# SSRC_v2.net
KiCad netlist of a schematic drawn in EasyEDA Pro
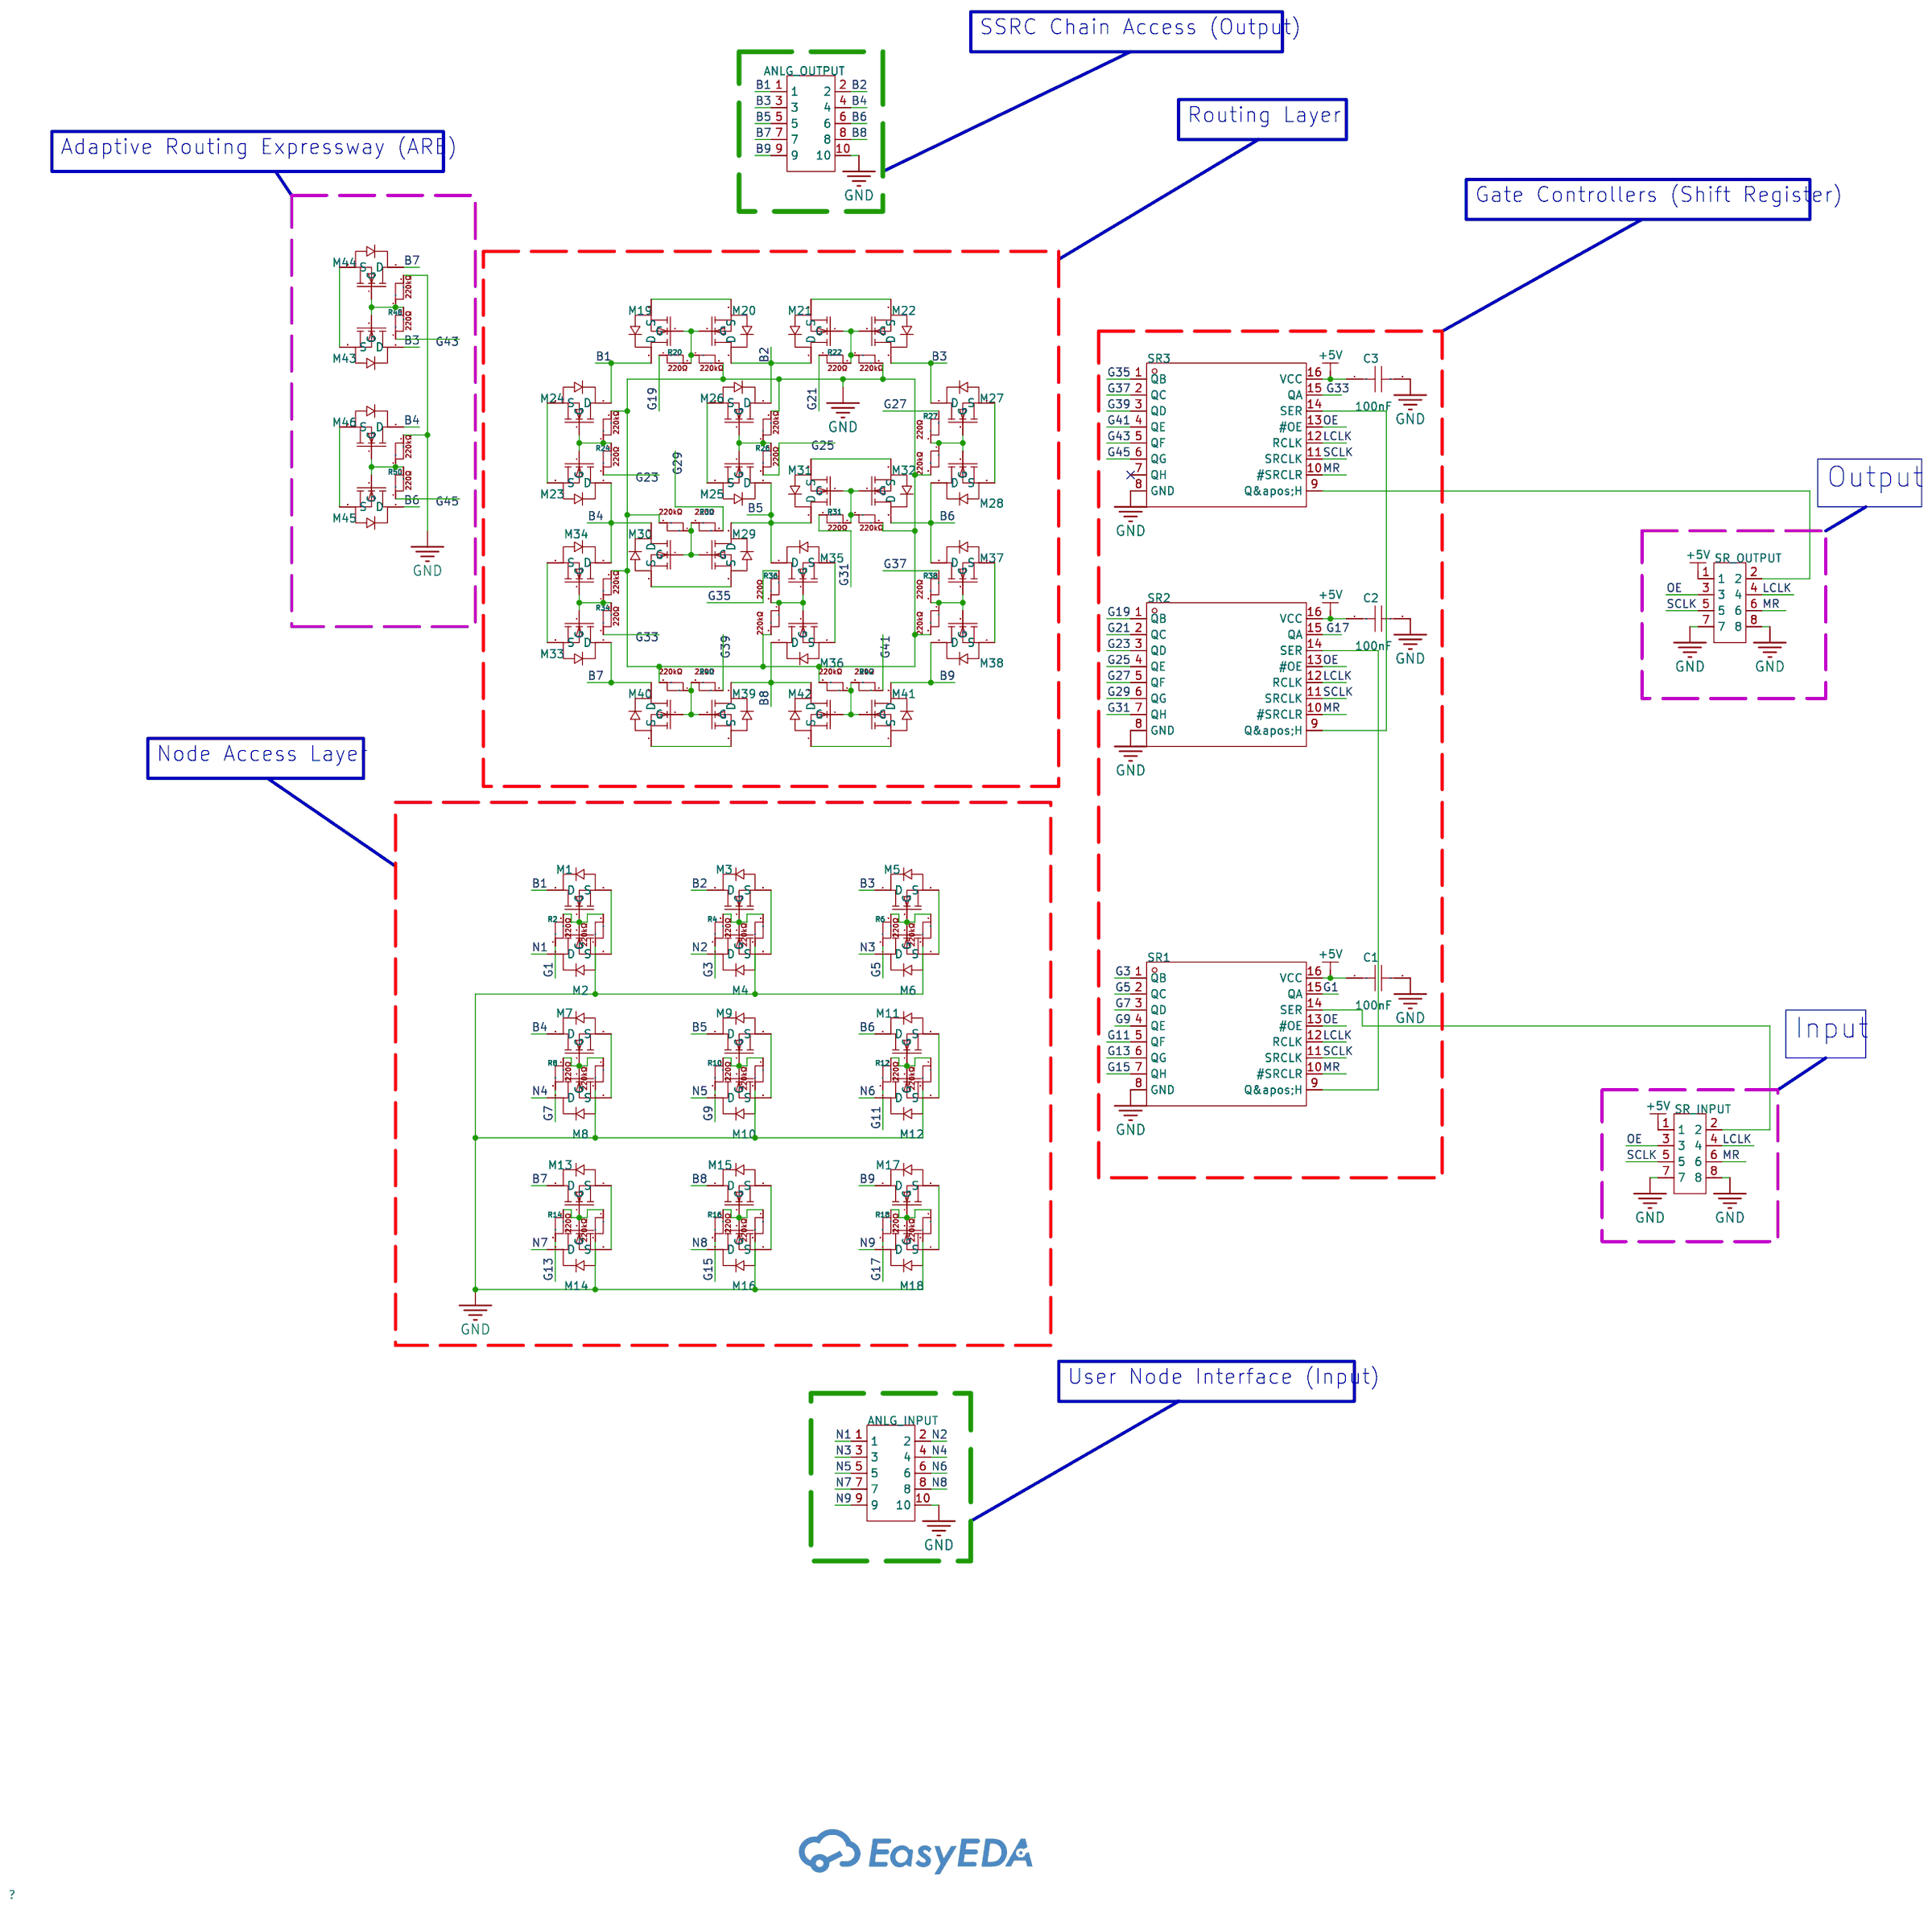
[diagram p0: schematic sheet]

(export (version "E")
  (design (tool "Eeschema 10.0.6"))
  (components
    (comp (ref "ANLG_INPUT")
      (value "PZ254V-12-10P")
      (footprint "easyedapro:HDR-TH_10P-P2.54-V-M-R2-C5-S2.54")
      (fields (field (name "Manufacturer") "XFCN(兴飞)"))
      (libsource (lib "easyedapro") (part "PZ254V-12-10P"))
    )
    (comp (ref "ANLG_OUTPUT")
      (value "PZ254V-12-10P")
      (footprint "easyedapro:HDR-TH_10P-P2.54-V-M-R2-C5-S2.54")
      (fields (field (name "Manufacturer") "XFCN(兴飞)"))
      (libsource (lib "easyedapro") (part "PZ254V-12-10P"))
    )
    (comp (ref "C1")
      (value "100nF")
      (footprint "easyedapro:C0805")
      (description "Capacitance:100nF Tolerance:±10% Tolerance:±10% Voltage Rating:50V Temperature Coefficient:X7R")
      (fields
        (field (name "Manufacturer Part") "CC0805KRX7R9BB104")
        (field (name "Manufacturer") "YAGEO(国巨)")
      )
      (libsource (lib "easyedapro") (part "CC0805KRX7R9BB104"))
    )
    (comp (ref "C2")
      (value "100nF")
      (footprint "easyedapro:C0805")
      (description "Capacitance:100nF Tolerance:±10% Tolerance:±10% Voltage Rating:50V Temperature Coefficient:X7R")
      (fields
        (field (name "Manufacturer Part") "CC0805KRX7R9BB104")
        (field (name "Manufacturer") "YAGEO(国巨)")
      )
      (libsource (lib "easyedapro") (part "CC0805KRX7R9BB104"))
    )
    (comp (ref "C3")
      (value "100nF")
      (footprint "easyedapro:C0805")
      (description "Capacitance:100nF Tolerance:±10% Tolerance:±10% Voltage Rating:50V Temperature Coefficient:X7R")
      (fields
        (field (name "Manufacturer Part") "CC0805KRX7R9BB104")
        (field (name "Manufacturer") "YAGEO(国巨)")
      )
      (libsource (lib "easyedapro") (part "CC0805KRX7R9BB104"))
    )
    (comp (ref "M1")
      (value "~")
      (footprint "easyedapro:SOT-23-3_L2.9-W1.3-P1.90-LS2.4-BR")
      (libsource (lib "easyedapro") (part "N_MOS"))
    )
    (comp (ref "M2")
      (value "~")
      (footprint "easyedapro:SOT-23-3_L2.9-W1.3-P1.90-LS2.4-BR")
      (libsource (lib "easyedapro") (part "N_MOS"))
    )
    (comp (ref "M3")
      (value "~")
      (footprint "easyedapro:SOT-23-3_L2.9-W1.3-P1.90-LS2.4-BR")
      (libsource (lib "easyedapro") (part "N_MOS"))
    )
    (comp (ref "M4")
      (value "~")
      (footprint "easyedapro:SOT-23-3_L2.9-W1.3-P1.90-LS2.4-BR")
      (libsource (lib "easyedapro") (part "N_MOS"))
    )
    (comp (ref "M5")
      (value "~")
      (footprint "easyedapro:SOT-23-3_L2.9-W1.3-P1.90-LS2.4-BR")
      (libsource (lib "easyedapro") (part "N_MOS"))
    )
    (comp (ref "M6")
      (value "~")
      (footprint "easyedapro:SOT-23-3_L2.9-W1.3-P1.90-LS2.4-BR")
      (libsource (lib "easyedapro") (part "N_MOS"))
    )
    (comp (ref "M7")
      (value "~")
      (footprint "easyedapro:SOT-23-3_L2.9-W1.3-P1.90-LS2.4-BR")
      (libsource (lib "easyedapro") (part "N_MOS"))
    )
    (comp (ref "M8")
      (value "~")
      (footprint "easyedapro:SOT-23-3_L2.9-W1.3-P1.90-LS2.4-BR")
      (libsource (lib "easyedapro") (part "N_MOS"))
    )
    (comp (ref "M9")
      (value "~")
      (footprint "easyedapro:SOT-23-3_L2.9-W1.3-P1.90-LS2.4-BR")
      (libsource (lib "easyedapro") (part "N_MOS"))
    )
    (comp (ref "M10")
      (value "~")
      (footprint "easyedapro:SOT-23-3_L2.9-W1.3-P1.90-LS2.4-BR")
      (libsource (lib "easyedapro") (part "N_MOS"))
    )
    (comp (ref "M11")
      (value "~")
      (footprint "easyedapro:SOT-23-3_L2.9-W1.3-P1.90-LS2.4-BR")
      (libsource (lib "easyedapro") (part "N_MOS"))
    )
    (comp (ref "M12")
      (value "~")
      (footprint "easyedapro:SOT-23-3_L2.9-W1.3-P1.90-LS2.4-BR")
      (libsource (lib "easyedapro") (part "N_MOS"))
    )
    (comp (ref "M13")
      (value "~")
      (footprint "easyedapro:SOT-23-3_L2.9-W1.3-P1.90-LS2.4-BR")
      (libsource (lib "easyedapro") (part "N_MOS"))
    )
    (comp (ref "M14")
      (value "~")
      (footprint "easyedapro:SOT-23-3_L2.9-W1.3-P1.90-LS2.4-BR")
      (libsource (lib "easyedapro") (part "N_MOS"))
    )
    (comp (ref "M15")
      (value "~")
      (footprint "easyedapro:SOT-23-3_L2.9-W1.3-P1.90-LS2.4-BR")
      (libsource (lib "easyedapro") (part "N_MOS"))
    )
    (comp (ref "M16")
      (value "~")
      (footprint "easyedapro:SOT-23-3_L2.9-W1.3-P1.90-LS2.4-BR")
      (libsource (lib "easyedapro") (part "N_MOS"))
    )
    (comp (ref "M17")
      (value "~")
      (footprint "easyedapro:SOT-23-3_L2.9-W1.3-P1.90-LS2.4-BR")
      (libsource (lib "easyedapro") (part "N_MOS"))
    )
    (comp (ref "M18")
      (value "~")
      (footprint "easyedapro:SOT-23-3_L2.9-W1.3-P1.90-LS2.4-BR")
      (libsource (lib "easyedapro") (part "N_MOS"))
    )
    (comp (ref "M19")
      (value "~")
      (footprint "easyedapro:SOT-23-3_L2.9-W1.3-P1.90-LS2.4-BR")
      (libsource (lib "easyedapro") (part "N_MOS"))
    )
    (comp (ref "M20")
      (value "~")
      (footprint "easyedapro:SOT-23-3_L2.9-W1.3-P1.90-LS2.4-BR")
      (libsource (lib "easyedapro") (part "N_MOS"))
    )
    (comp (ref "M21")
      (value "~")
      (footprint "easyedapro:SOT-23-3_L2.9-W1.3-P1.90-LS2.4-BR")
      (libsource (lib "easyedapro") (part "N_MOS"))
    )
    (comp (ref "M22")
      (value "~")
      (footprint "easyedapro:SOT-23-3_L2.9-W1.3-P1.90-LS2.4-BR")
      (libsource (lib "easyedapro") (part "N_MOS"))
    )
    (comp (ref "M23")
      (value "~")
      (footprint "easyedapro:SOT-23-3_L2.9-W1.3-P1.90-LS2.4-BR")
      (libsource (lib "easyedapro") (part "N_MOS"))
    )
    (comp (ref "M24")
      (value "~")
      (footprint "easyedapro:SOT-23-3_L2.9-W1.3-P1.90-LS2.4-BR")
      (libsource (lib "easyedapro") (part "N_MOS"))
    )
    (comp (ref "M25")
      (value "~")
      (footprint "easyedapro:SOT-23-3_L2.9-W1.3-P1.90-LS2.4-BR")
      (libsource (lib "easyedapro") (part "N_MOS"))
    )
    (comp (ref "M26")
      (value "~")
      (footprint "easyedapro:SOT-23-3_L2.9-W1.3-P1.90-LS2.4-BR")
      (libsource (lib "easyedapro") (part "N_MOS"))
    )
    (comp (ref "M27")
      (value "~")
      (footprint "easyedapro:SOT-23-3_L2.9-W1.3-P1.90-LS2.4-BR")
      (libsource (lib "easyedapro") (part "N_MOS"))
    )
    (comp (ref "M28")
      (value "~")
      (footprint "easyedapro:SOT-23-3_L2.9-W1.3-P1.90-LS2.4-BR")
      (libsource (lib "easyedapro") (part "N_MOS"))
    )
    (comp (ref "M29")
      (value "~")
      (footprint "easyedapro:SOT-23-3_L2.9-W1.3-P1.90-LS2.4-BR")
      (libsource (lib "easyedapro") (part "N_MOS"))
    )
    (comp (ref "M30")
      (value "~")
      (footprint "easyedapro:SOT-23-3_L2.9-W1.3-P1.90-LS2.4-BR")
      (libsource (lib "easyedapro") (part "N_MOS"))
    )
    (comp (ref "M31")
      (value "~")
      (footprint "easyedapro:SOT-23-3_L2.9-W1.3-P1.90-LS2.4-BR")
      (libsource (lib "easyedapro") (part "N_MOS"))
    )
    (comp (ref "M32")
      (value "~")
      (footprint "easyedapro:SOT-23-3_L2.9-W1.3-P1.90-LS2.4-BR")
      (libsource (lib "easyedapro") (part "N_MOS"))
    )
    (comp (ref "M33")
      (value "~")
      (footprint "easyedapro:SOT-23-3_L2.9-W1.3-P1.90-LS2.4-BR")
      (libsource (lib "easyedapro") (part "N_MOS"))
    )
    (comp (ref "M34")
      (value "~")
      (footprint "easyedapro:SOT-23-3_L2.9-W1.3-P1.90-LS2.4-BR")
      (libsource (lib "easyedapro") (part "N_MOS"))
    )
    (comp (ref "M35")
      (value "~")
      (footprint "easyedapro:SOT-23-3_L2.9-W1.3-P1.90-LS2.4-BR")
      (libsource (lib "easyedapro") (part "N_MOS"))
    )
    (comp (ref "M36")
      (value "~")
      (footprint "easyedapro:SOT-23-3_L2.9-W1.3-P1.90-LS2.4-BR")
      (libsource (lib "easyedapro") (part "N_MOS"))
    )
    (comp (ref "M37")
      (value "~")
      (footprint "easyedapro:SOT-23-3_L2.9-W1.3-P1.90-LS2.4-BR")
      (libsource (lib "easyedapro") (part "N_MOS"))
    )
    (comp (ref "M38")
      (value "~")
      (footprint "easyedapro:SOT-23-3_L2.9-W1.3-P1.90-LS2.4-BR")
      (libsource (lib "easyedapro") (part "N_MOS"))
    )
    (comp (ref "M39")
      (value "~")
      (footprint "easyedapro:SOT-23-3_L2.9-W1.3-P1.90-LS2.4-BR")
      (libsource (lib "easyedapro") (part "N_MOS"))
    )
    (comp (ref "M40")
      (value "~")
      (footprint "easyedapro:SOT-23-3_L2.9-W1.3-P1.90-LS2.4-BR")
      (libsource (lib "easyedapro") (part "N_MOS"))
    )
    (comp (ref "M41")
      (value "~")
      (footprint "easyedapro:SOT-23-3_L2.9-W1.3-P1.90-LS2.4-BR")
      (libsource (lib "easyedapro") (part "N_MOS"))
    )
    (comp (ref "M42")
      (value "~")
      (footprint "easyedapro:SOT-23-3_L2.9-W1.3-P1.90-LS2.4-BR")
      (libsource (lib "easyedapro") (part "N_MOS"))
    )
    (comp (ref "M43")
      (value "~")
      (footprint "easyedapro:SOT-23-3_L2.9-W1.3-P1.90-LS2.4-BR")
      (libsource (lib "easyedapro") (part "N_MOS"))
    )
    (comp (ref "M44")
      (value "~")
      (footprint "easyedapro:SOT-23-3_L2.9-W1.3-P1.90-LS2.4-BR")
      (libsource (lib "easyedapro") (part "N_MOS"))
    )
    (comp (ref "M45")
      (value "~")
      (footprint "easyedapro:SOT-23-3_L2.9-W1.3-P1.90-LS2.4-BR")
      (libsource (lib "easyedapro") (part "N_MOS"))
    )
    (comp (ref "M46")
      (value "~")
      (footprint "easyedapro:SOT-23-3_L2.9-W1.3-P1.90-LS2.4-BR")
      (libsource (lib "easyedapro") (part "N_MOS"))
    )
    (comp (ref "R1")
      (value "~")
      (footprint "easyedapro:RC1206FR-07220KL")
      (libsource (lib "easyedapro") (part "RC1206FR-07220KL"))
    )
    (comp (ref "R2")
      (value "~")
      (footprint "easyedapro:RC1206FR-1022RL")
      (libsource (lib "easyedapro") (part "RC1206FR-10220RL (mini schem)"))
    )
    (comp (ref "R3")
      (value "~")
      (footprint "easyedapro:RC1206FR-07220KL")
      (libsource (lib "easyedapro") (part "RC1206FR-07220KL"))
    )
    (comp (ref "R4")
      (value "~")
      (footprint "easyedapro:RC1206FR-1022RL")
      (libsource (lib "easyedapro") (part "RC1206FR-10220RL (mini schem)"))
    )
    (comp (ref "R5")
      (value "~")
      (footprint "easyedapro:RC1206FR-07220KL")
      (libsource (lib "easyedapro") (part "RC1206FR-07220KL"))
    )
    (comp (ref "R6")
      (value "~")
      (footprint "easyedapro:RC1206FR-1022RL")
      (libsource (lib "easyedapro") (part "RC1206FR-10220RL (mini schem)"))
    )
    (comp (ref "R7")
      (value "~")
      (footprint "easyedapro:RC1206FR-07220KL")
      (libsource (lib "easyedapro") (part "RC1206FR-07220KL"))
    )
    (comp (ref "R8")
      (value "~")
      (footprint "easyedapro:RC1206FR-1022RL")
      (libsource (lib "easyedapro") (part "RC1206FR-10220RL (mini schem)"))
    )
    (comp (ref "R9")
      (value "~")
      (footprint "easyedapro:RC1206FR-07220KL")
      (libsource (lib "easyedapro") (part "RC1206FR-07220KL"))
    )
    (comp (ref "R10")
      (value "~")
      (footprint "easyedapro:RC1206FR-1022RL")
      (libsource (lib "easyedapro") (part "RC1206FR-10220RL (mini schem)"))
    )
    (comp (ref "R11")
      (value "~")
      (footprint "easyedapro:RC1206FR-07220KL")
      (libsource (lib "easyedapro") (part "RC1206FR-07220KL"))
    )
    (comp (ref "R12")
      (value "~")
      (footprint "easyedapro:RC1206FR-1022RL")
      (libsource (lib "easyedapro") (part "RC1206FR-10220RL (mini schem)"))
    )
    (comp (ref "R13")
      (value "~")
      (footprint "easyedapro:RC1206FR-07220KL")
      (libsource (lib "easyedapro") (part "RC1206FR-07220KL"))
    )
    (comp (ref "R14")
      (value "~")
      (footprint "easyedapro:RC1206FR-1022RL")
      (libsource (lib "easyedapro") (part "RC1206FR-10220RL (mini schem)"))
    )
    (comp (ref "R15")
      (value "~")
      (footprint "easyedapro:RC1206FR-07220KL")
      (libsource (lib "easyedapro") (part "RC1206FR-07220KL"))
    )
    (comp (ref "R16")
      (value "~")
      (footprint "easyedapro:RC1206FR-1022RL")
      (libsource (lib "easyedapro") (part "RC1206FR-10220RL (mini schem)"))
    )
    (comp (ref "R17")
      (value "~")
      (footprint "easyedapro:RC1206FR-07220KL")
      (libsource (lib "easyedapro") (part "RC1206FR-07220KL"))
    )
    (comp (ref "R18")
      (value "~")
      (footprint "easyedapro:RC1206FR-1022RL")
      (libsource (lib "easyedapro") (part "RC1206FR-10220RL (mini schem)"))
    )
    (comp (ref "R19")
      (value "~")
      (footprint "easyedapro:RC1206FR-07220KL")
      (libsource (lib "easyedapro") (part "RC1206FR-07220KL"))
    )
    (comp (ref "R20")
      (value "~")
      (footprint "easyedapro:RC1206FR-1022RL")
      (libsource (lib "easyedapro") (part "RC1206FR-10220RL (mini schem)"))
    )
    (comp (ref "R21")
      (value "~")
      (footprint "easyedapro:RC1206FR-07220KL")
      (libsource (lib "easyedapro") (part "RC1206FR-07220KL"))
    )
    (comp (ref "R22")
      (value "~")
      (footprint "easyedapro:RC1206FR-1022RL")
      (libsource (lib "easyedapro") (part "RC1206FR-10220RL (mini schem)"))
    )
    (comp (ref "R23")
      (value "~")
      (footprint "easyedapro:RC1206FR-07220KL")
      (libsource (lib "easyedapro") (part "RC1206FR-07220KL"))
    )
    (comp (ref "R24")
      (value "~")
      (footprint "easyedapro:RC1206FR-1022RL")
      (libsource (lib "easyedapro") (part "RC1206FR-10220RL (mini schem)"))
    )
    (comp (ref "R25")
      (value "~")
      (footprint "easyedapro:RC1206FR-07220KL")
      (libsource (lib "easyedapro") (part "RC1206FR-07220KL"))
    )
    (comp (ref "R26")
      (value "~")
      (footprint "easyedapro:RC1206FR-1022RL")
      (libsource (lib "easyedapro") (part "RC1206FR-10220RL (mini schem)"))
    )
    (comp (ref "R27")
      (value "~")
      (footprint "easyedapro:RC1206FR-1022RL")
      (libsource (lib "easyedapro") (part "RC1206FR-10220RL (mini schem)"))
    )
    (comp (ref "R28")
      (value "~")
      (footprint "easyedapro:RC1206FR-07220KL")
      (libsource (lib "easyedapro") (part "RC1206FR-07220KL"))
    )
    (comp (ref "R29")
      (value "~")
      (footprint "easyedapro:RC1206FR-07220KL")
      (libsource (lib "easyedapro") (part "RC1206FR-07220KL"))
    )
    (comp (ref "R30")
      (value "~")
      (footprint "easyedapro:RC1206FR-1022RL")
      (libsource (lib "easyedapro") (part "RC1206FR-10220RL (mini schem)"))
    )
    (comp (ref "R31")
      (value "~")
      (footprint "easyedapro:RC1206FR-1022RL")
      (libsource (lib "easyedapro") (part "RC1206FR-10220RL (mini schem)"))
    )
    (comp (ref "R32")
      (value "~")
      (footprint "easyedapro:RC1206FR-07220KL")
      (libsource (lib "easyedapro") (part "RC1206FR-07220KL"))
    )
    (comp (ref "R33")
      (value "~")
      (footprint "easyedapro:RC1206FR-07220KL")
      (libsource (lib "easyedapro") (part "RC1206FR-07220KL"))
    )
    (comp (ref "R34")
      (value "~")
      (footprint "easyedapro:RC1206FR-1022RL")
      (libsource (lib "easyedapro") (part "RC1206FR-10220RL (mini schem)"))
    )
    (comp (ref "R35")
      (value "~")
      (footprint "easyedapro:RC1206FR-07220KL")
      (libsource (lib "easyedapro") (part "RC1206FR-07220KL"))
    )
    (comp (ref "R36")
      (value "~")
      (footprint "easyedapro:RC1206FR-1022RL")
      (libsource (lib "easyedapro") (part "RC1206FR-10220RL (mini schem)"))
    )
    (comp (ref "R37")
      (value "~")
      (footprint "easyedapro:RC1206FR-07220KL")
      (libsource (lib "easyedapro") (part "RC1206FR-07220KL"))
    )
    (comp (ref "R38")
      (value "~")
      (footprint "easyedapro:RC1206FR-1022RL")
      (libsource (lib "easyedapro") (part "RC1206FR-10220RL (mini schem)"))
    )
    (comp (ref "R39")
      (value "~")
      (footprint "easyedapro:RC1206FR-07220KL")
      (libsource (lib "easyedapro") (part "RC1206FR-07220KL"))
    )
    (comp (ref "R40")
      (value "~")
      (footprint "easyedapro:RC1206FR-1022RL")
      (libsource (lib "easyedapro") (part "RC1206FR-10220RL (mini schem)"))
    )
    (comp (ref "R41")
      (value "~")
      (footprint "easyedapro:RC1206FR-07220KL")
      (libsource (lib "easyedapro") (part "RC1206FR-07220KL"))
    )
    (comp (ref "R42")
      (value "~")
      (footprint "easyedapro:RC1206FR-1022RL")
      (libsource (lib "easyedapro") (part "RC1206FR-10220RL (mini schem)"))
    )
    (comp (ref "R47")
      (value "~")
      (footprint "easyedapro:RC1206FR-07220KL")
      (libsource (lib "easyedapro") (part "RC1206FR-07220KL"))
    )
    (comp (ref "R48")
      (value "~")
      (footprint "easyedapro:RC1206FR-1022RL")
      (libsource (lib "easyedapro") (part "RC1206FR-10220RL (mini schem)"))
    )
    (comp (ref "R49")
      (value "~")
      (footprint "easyedapro:RC1206FR-07220KL")
      (libsource (lib "easyedapro") (part "RC1206FR-07220KL"))
    )
    (comp (ref "R50")
      (value "~")
      (footprint "easyedapro:RC1206FR-1022RL")
      (libsource (lib "easyedapro") (part "RC1206FR-10220RL (mini schem)"))
    )
    (comp (ref "SR1")
      (value "SN74HC595NSR")
      (footprint "easyedapro:SOP-16_L10.3-W5.4-P1.27-LS7.8-BL")
      (fields (field (name "Manufacturer") "TI(德州仪器)"))
      (libsource (lib "easyedapro") (part "SN74HC595NSR"))
    )
    (comp (ref "SR2")
      (value "SN74HC595NSR")
      (footprint "easyedapro:SOP-16_L10.3-W5.4-P1.27-LS7.8-BL")
      (fields (field (name "Manufacturer") "TI(德州仪器)"))
      (libsource (lib "easyedapro") (part "SN74HC595NSR"))
    )
    (comp (ref "SR3")
      (value "SN74HC595NSR")
      (footprint "easyedapro:SOP-16_L10.3-W5.4-P1.27-LS7.8-BL")
      (fields (field (name "Manufacturer") "TI(德州仪器)"))
      (libsource (lib "easyedapro") (part "SN74HC595NSR"))
    )
    (comp (ref "SR_INPUT")
      (value "PZ254V-12-8P")
      (footprint "easyedapro:HDR-TH_8P-P2.54-V-M-R2-C4-S2.54")
      (fields (field (name "Manufacturer") "XFCN(兴飞)"))
      (libsource (lib "easyedapro") (part "PZ254V-12-8P"))
    )
    (comp (ref "SR_OUTPUT")
      (value "PZ254V-12-8P")
      (footprint "easyedapro:HDR-TH_8P-P2.54-V-M-R2-C4-S2.54")
      (fields (field (name "Manufacturer") "XFCN(兴飞)"))
      (libsource (lib "easyedapro") (part "PZ254V-12-8P"))
    )
  )
  (nets
    (net (code "1") (name "+5V") (class "Default")
      (node (ref "C1") (pin "1") (pinfunction "1_1") (pintype "unspecified"))
      (node (ref "C2") (pin "1") (pinfunction "1_1") (pintype "unspecified"))
      (node (ref "C3") (pin "1") (pinfunction "1_1") (pintype "unspecified"))
      (node (ref "SR1") (pin "16") (pinfunction "VCC_16") (pintype "unspecified"))
      (node (ref "SR2") (pin "16") (pinfunction "VCC_16") (pintype "unspecified"))
      (node (ref "SR3") (pin "16") (pinfunction "VCC_16") (pintype "unspecified"))
      (node (ref "SR_INPUT") (pin "1") (pinfunction "1_1") (pintype "unspecified"))
      (node (ref "SR_OUTPUT") (pin "1") (pinfunction "1_1") (pintype "unspecified"))
    )
    (net (code "2") (name "/B1") (class "Default")
      (node (ref "ANLG_OUTPUT") (pin "1") (pinfunction "1_1") (pintype "unspecified"))
      (node (ref "M1") (pin "3") (pinfunction "D_3") (pintype "input"))
      (node (ref "M19") (pin "3") (pinfunction "D_3") (pintype "input"))
      (node (ref "M24") (pin "3") (pinfunction "D_3") (pintype "input"))
    )
    (net (code "3") (name "/B2") (class "Default")
      (node (ref "ANLG_OUTPUT") (pin "2") (pinfunction "2_2") (pintype "unspecified"))
      (node (ref "M20") (pin "3") (pinfunction "D_3") (pintype "input"))
      (node (ref "M21") (pin "3") (pinfunction "D_3") (pintype "input"))
      (node (ref "M26") (pin "3") (pinfunction "D_3") (pintype "input"))
      (node (ref "M3") (pin "3") (pinfunction "D_3") (pintype "input"))
    )
    (net (code "4") (name "/B3") (class "Default")
      (node (ref "ANLG_OUTPUT") (pin "3") (pinfunction "3_3") (pintype "unspecified"))
      (node (ref "M22") (pin "3") (pinfunction "D_3") (pintype "input"))
      (node (ref "M27") (pin "3") (pinfunction "D_3") (pintype "input"))
      (node (ref "M43") (pin "3") (pinfunction "D_3") (pintype "input"))
      (node (ref "M5") (pin "3") (pinfunction "D_3") (pintype "input"))
    )
    (net (code "5") (name "/B4") (class "Default")
      (node (ref "ANLG_OUTPUT") (pin "4") (pinfunction "4_4") (pintype "unspecified"))
      (node (ref "M23") (pin "3") (pinfunction "D_3") (pintype "input"))
      (node (ref "M30") (pin "3") (pinfunction "D_3") (pintype "input"))
      (node (ref "M34") (pin "3") (pinfunction "D_3") (pintype "input"))
      (node (ref "M46") (pin "3") (pinfunction "D_3") (pintype "input"))
      (node (ref "M7") (pin "3") (pinfunction "D_3") (pintype "input"))
    )
    (net (code "6") (name "/B5") (class "Default")
      (node (ref "ANLG_OUTPUT") (pin "5") (pinfunction "5_5") (pintype "unspecified"))
      (node (ref "M25") (pin "3") (pinfunction "D_3") (pintype "input"))
      (node (ref "M29") (pin "3") (pinfunction "D_3") (pintype "input"))
      (node (ref "M31") (pin "3") (pinfunction "D_3") (pintype "input"))
      (node (ref "M35") (pin "3") (pinfunction "D_3") (pintype "input"))
      (node (ref "M9") (pin "3") (pinfunction "D_3") (pintype "input"))
    )
    (net (code "7") (name "/B6") (class "Default")
      (node (ref "ANLG_OUTPUT") (pin "6") (pinfunction "6_6") (pintype "unspecified"))
      (node (ref "M11") (pin "3") (pinfunction "D_3") (pintype "input"))
      (node (ref "M28") (pin "3") (pinfunction "D_3") (pintype "input"))
      (node (ref "M32") (pin "3") (pinfunction "D_3") (pintype "input"))
      (node (ref "M37") (pin "3") (pinfunction "D_3") (pintype "input"))
      (node (ref "M45") (pin "3") (pinfunction "D_3") (pintype "input"))
    )
    (net (code "8") (name "/B7") (class "Default")
      (node (ref "ANLG_OUTPUT") (pin "7") (pinfunction "7_7") (pintype "unspecified"))
      (node (ref "M13") (pin "3") (pinfunction "D_3") (pintype "input"))
      (node (ref "M33") (pin "3") (pinfunction "D_3") (pintype "input"))
      (node (ref "M40") (pin "3") (pinfunction "D_3") (pintype "input"))
      (node (ref "M44") (pin "3") (pinfunction "D_3") (pintype "input"))
    )
    (net (code "9") (name "/B8") (class "Default")
      (node (ref "ANLG_OUTPUT") (pin "8") (pinfunction "8_8") (pintype "unspecified"))
      (node (ref "M15") (pin "3") (pinfunction "D_3") (pintype "input"))
      (node (ref "M36") (pin "3") (pinfunction "D_3") (pintype "input"))
      (node (ref "M39") (pin "3") (pinfunction "D_3") (pintype "input"))
      (node (ref "M42") (pin "3") (pinfunction "D_3") (pintype "input"))
    )
    (net (code "10") (name "/B9") (class "Default")
      (node (ref "ANLG_OUTPUT") (pin "9") (pinfunction "9_9") (pintype "unspecified"))
      (node (ref "M17") (pin "3") (pinfunction "D_3") (pintype "input"))
      (node (ref "M38") (pin "3") (pinfunction "D_3") (pintype "input"))
      (node (ref "M41") (pin "3") (pinfunction "D_3") (pintype "input"))
    )
    (net (code "11") (name "/G1") (class "Default")
      (node (ref "R2") (pin "1") (pinfunction "1_1") (pintype "input"))
      (node (ref "SR1") (pin "15") (pinfunction "QA_15") (pintype "unspecified"))
    )
    (net (code "12") (name "/G3") (class "Default")
      (node (ref "R4") (pin "1") (pinfunction "1_1") (pintype "input"))
      (node (ref "SR1") (pin "1") (pinfunction "QB_1") (pintype "unspecified"))
    )
    (net (code "13") (name "/G5") (class "Default")
      (node (ref "R6") (pin "1") (pinfunction "1_1") (pintype "input"))
      (node (ref "SR1") (pin "2") (pinfunction "QC_2") (pintype "unspecified"))
    )
    (net (code "14") (name "/G7") (class "Default")
      (node (ref "R8") (pin "1") (pinfunction "1_1") (pintype "input"))
      (node (ref "SR1") (pin "3") (pinfunction "QD_3") (pintype "unspecified"))
    )
    (net (code "15") (name "/G9") (class "Default")
      (node (ref "R10") (pin "1") (pinfunction "1_1") (pintype "input"))
      (node (ref "SR1") (pin "4") (pinfunction "QE_4") (pintype "unspecified"))
    )
    (net (code "16") (name "/G11") (class "Default")
      (node (ref "R12") (pin "1") (pinfunction "1_1") (pintype "input"))
      (node (ref "SR1") (pin "5") (pinfunction "QF_5") (pintype "unspecified"))
    )
    (net (code "17") (name "/G13") (class "Default")
      (node (ref "R14") (pin "1") (pinfunction "1_1") (pintype "input"))
      (node (ref "SR1") (pin "6") (pinfunction "QG_6") (pintype "unspecified"))
    )
    (net (code "18") (name "/G15") (class "Default")
      (node (ref "R16") (pin "1") (pinfunction "1_1") (pintype "input"))
      (node (ref "SR1") (pin "7") (pinfunction "QH_7") (pintype "unspecified"))
    )
    (net (code "19") (name "/G17") (class "Default")
      (node (ref "R18") (pin "1") (pinfunction "1_1") (pintype "input"))
      (node (ref "SR2") (pin "15") (pinfunction "QA_15") (pintype "unspecified"))
    )
    (net (code "20") (name "/G19") (class "Default")
      (node (ref "R20") (pin "1") (pinfunction "1_1") (pintype "input"))
      (node (ref "SR2") (pin "1") (pinfunction "QB_1") (pintype "unspecified"))
    )
    (net (code "21") (name "/G21") (class "Default")
      (node (ref "R22") (pin "1") (pinfunction "1_1") (pintype "input"))
      (node (ref "SR2") (pin "2") (pinfunction "QC_2") (pintype "unspecified"))
    )
    (net (code "22") (name "/G23") (class "Default")
      (node (ref "R24") (pin "1") (pinfunction "1_1") (pintype "input"))
      (node (ref "SR2") (pin "3") (pinfunction "QD_3") (pintype "unspecified"))
    )
    (net (code "23") (name "/G25") (class "Default")
      (node (ref "R26") (pin "1") (pinfunction "1_1") (pintype "input"))
      (node (ref "SR2") (pin "4") (pinfunction "QE_4") (pintype "unspecified"))
    )
    (net (code "24") (name "/G27") (class "Default")
      (node (ref "R27") (pin "1") (pinfunction "1_1") (pintype "input"))
      (node (ref "SR2") (pin "5") (pinfunction "QF_5") (pintype "unspecified"))
    )
    (net (code "25") (name "/G29") (class "Default")
      (node (ref "R30") (pin "1") (pinfunction "1_1") (pintype "input"))
      (node (ref "SR2") (pin "6") (pinfunction "QG_6") (pintype "unspecified"))
    )
    (net (code "26") (name "/G31") (class "Default")
      (node (ref "R31") (pin "1") (pinfunction "1_1") (pintype "input"))
      (node (ref "SR2") (pin "7") (pinfunction "QH_7") (pintype "unspecified"))
    )
    (net (code "27") (name "/G33") (class "Default")
      (node (ref "R34") (pin "1") (pinfunction "1_1") (pintype "input"))
      (node (ref "SR3") (pin "15") (pinfunction "QA_15") (pintype "unspecified"))
    )
    (net (code "28") (name "/G35") (class "Default")
      (node (ref "R36") (pin "1") (pinfunction "1_1") (pintype "input"))
      (node (ref "SR3") (pin "1") (pinfunction "QB_1") (pintype "unspecified"))
    )
    (net (code "29") (name "/G37") (class "Default")
      (node (ref "R38") (pin "1") (pinfunction "1_1") (pintype "input"))
      (node (ref "SR3") (pin "2") (pinfunction "QC_2") (pintype "unspecified"))
    )
    (net (code "30") (name "/G39") (class "Default")
      (node (ref "R40") (pin "1") (pinfunction "1_1") (pintype "input"))
      (node (ref "SR3") (pin "3") (pinfunction "QD_3") (pintype "unspecified"))
    )
    (net (code "31") (name "/G41") (class "Default")
      (node (ref "R42") (pin "1") (pinfunction "1_1") (pintype "input"))
      (node (ref "SR3") (pin "4") (pinfunction "QE_4") (pintype "unspecified"))
    )
    (net (code "32") (name "/G43") (class "Default")
      (node (ref "R48") (pin "1") (pinfunction "1_1") (pintype "input"))
      (node (ref "SR3") (pin "5") (pinfunction "QF_5") (pintype "unspecified"))
    )
    (net (code "33") (name "/G45") (class "Default")
      (node (ref "R50") (pin "1") (pinfunction "1_1") (pintype "input"))
      (node (ref "SR3") (pin "6") (pinfunction "QG_6") (pintype "unspecified"))
    )
    (net (code "34") (name "/LCLK") (class "Default")
      (node (ref "SR1") (pin "12") (pinfunction "RCLK_12") (pintype "unspecified"))
      (node (ref "SR2") (pin "12") (pinfunction "RCLK_12") (pintype "unspecified"))
      (node (ref "SR3") (pin "12") (pinfunction "RCLK_12") (pintype "unspecified"))
      (node (ref "SR_INPUT") (pin "4") (pinfunction "4_4") (pintype "unspecified"))
      (node (ref "SR_OUTPUT") (pin "4") (pinfunction "4_4") (pintype "unspecified"))
    )
    (net (code "35") (name "/MR") (class "Default")
      (node (ref "SR1") (pin "10") (pinfunction "#SRCLR_10") (pintype "unspecified"))
      (node (ref "SR2") (pin "10") (pinfunction "#SRCLR_10") (pintype "unspecified"))
      (node (ref "SR3") (pin "10") (pinfunction "#SRCLR_10") (pintype "unspecified"))
      (node (ref "SR_INPUT") (pin "6") (pinfunction "6_6") (pintype "unspecified"))
      (node (ref "SR_OUTPUT") (pin "6") (pinfunction "6_6") (pintype "unspecified"))
    )
    (net (code "36") (name "/N1") (class "Default")
      (node (ref "ANLG_INPUT") (pin "1") (pinfunction "1_1") (pintype "unspecified"))
      (node (ref "M2") (pin "3") (pinfunction "D_3") (pintype "input"))
    )
    (net (code "37") (name "/N2") (class "Default")
      (node (ref "ANLG_INPUT") (pin "2") (pinfunction "2_2") (pintype "unspecified"))
      (node (ref "M4") (pin "3") (pinfunction "D_3") (pintype "input"))
    )
    (net (code "38") (name "/N3") (class "Default")
      (node (ref "ANLG_INPUT") (pin "3") (pinfunction "3_3") (pintype "unspecified"))
      (node (ref "M6") (pin "3") (pinfunction "D_3") (pintype "input"))
    )
    (net (code "39") (name "/N4") (class "Default")
      (node (ref "ANLG_INPUT") (pin "4") (pinfunction "4_4") (pintype "unspecified"))
      (node (ref "M8") (pin "3") (pinfunction "D_3") (pintype "input"))
    )
    (net (code "40") (name "/N5") (class "Default")
      (node (ref "ANLG_INPUT") (pin "5") (pinfunction "5_5") (pintype "unspecified"))
      (node (ref "M10") (pin "3") (pinfunction "D_3") (pintype "input"))
    )
    (net (code "41") (name "/N6") (class "Default")
      (node (ref "ANLG_INPUT") (pin "6") (pinfunction "6_6") (pintype "unspecified"))
      (node (ref "M12") (pin "3") (pinfunction "D_3") (pintype "input"))
    )
    (net (code "42") (name "/N7") (class "Default")
      (node (ref "ANLG_INPUT") (pin "7") (pinfunction "7_7") (pintype "unspecified"))
      (node (ref "M14") (pin "3") (pinfunction "D_3") (pintype "input"))
    )
    (net (code "43") (name "/N8") (class "Default")
      (node (ref "ANLG_INPUT") (pin "8") (pinfunction "8_8") (pintype "unspecified"))
      (node (ref "M16") (pin "3") (pinfunction "D_3") (pintype "input"))
    )
    (net (code "44") (name "/N9") (class "Default")
      (node (ref "ANLG_INPUT") (pin "9") (pinfunction "9_9") (pintype "unspecified"))
      (node (ref "M18") (pin "3") (pinfunction "D_3") (pintype "input"))
    )
    (net (code "45") (name "/OE") (class "Default")
      (node (ref "SR1") (pin "13") (pinfunction "#OE_13") (pintype "unspecified"))
      (node (ref "SR2") (pin "13") (pinfunction "#OE_13") (pintype "unspecified"))
      (node (ref "SR3") (pin "13") (pinfunction "#OE_13") (pintype "unspecified"))
      (node (ref "SR_INPUT") (pin "3") (pinfunction "3_3") (pintype "unspecified"))
      (node (ref "SR_OUTPUT") (pin "3") (pinfunction "3_3") (pintype "unspecified"))
    )
    (net (code "46") (name "/SCLK") (class "Default")
      (node (ref "SR1") (pin "11") (pinfunction "SRCLK_11") (pintype "unspecified"))
      (node (ref "SR2") (pin "11") (pinfunction "SRCLK_11") (pintype "unspecified"))
      (node (ref "SR3") (pin "11") (pinfunction "SRCLK_11") (pintype "unspecified"))
      (node (ref "SR_INPUT") (pin "5") (pinfunction "5_5") (pintype "unspecified"))
      (node (ref "SR_OUTPUT") (pin "5") (pinfunction "5_5") (pintype "unspecified"))
    )
    (net (code "47") (name "GND") (class "Default")
      (node (ref "ANLG_INPUT") (pin "10") (pinfunction "10_10") (pintype "unspecified"))
      (node (ref "ANLG_OUTPUT") (pin "10") (pinfunction "10_10") (pintype "unspecified"))
      (node (ref "C1") (pin "2") (pinfunction "2_2") (pintype "unspecified"))
      (node (ref "C2") (pin "2") (pinfunction "2_2") (pintype "unspecified"))
      (node (ref "C3") (pin "2") (pinfunction "2_2") (pintype "unspecified"))
      (node (ref "R1") (pin "2") (pinfunction "1_2") (pintype "input"))
      (node (ref "R11") (pin "2") (pinfunction "1_2") (pintype "input"))
      (node (ref "R13") (pin "2") (pinfunction "1_2") (pintype "input"))
      (node (ref "R15") (pin "2") (pinfunction "1_2") (pintype "input"))
      (node (ref "R17") (pin "2") (pinfunction "1_2") (pintype "input"))
      (node (ref "R19") (pin "2") (pinfunction "1_2") (pintype "input"))
      (node (ref "R21") (pin "2") (pinfunction "1_2") (pintype "input"))
      (node (ref "R23") (pin "2") (pinfunction "1_2") (pintype "input"))
      (node (ref "R25") (pin "2") (pinfunction "1_2") (pintype "input"))
      (node (ref "R28") (pin "2") (pinfunction "1_2") (pintype "input"))
      (node (ref "R29") (pin "2") (pinfunction "1_2") (pintype "input"))
      (node (ref "R3") (pin "2") (pinfunction "1_2") (pintype "input"))
      (node (ref "R32") (pin "2") (pinfunction "1_2") (pintype "input"))
      (node (ref "R33") (pin "2") (pinfunction "1_2") (pintype "input"))
      (node (ref "R35") (pin "2") (pinfunction "1_2") (pintype "input"))
      (node (ref "R37") (pin "2") (pinfunction "1_2") (pintype "input"))
      (node (ref "R39") (pin "2") (pinfunction "1_2") (pintype "input"))
      (node (ref "R41") (pin "2") (pinfunction "1_2") (pintype "input"))
      (node (ref "R47") (pin "2") (pinfunction "1_2") (pintype "input"))
      (node (ref "R49") (pin "2") (pinfunction "1_2") (pintype "input"))
      (node (ref "R5") (pin "2") (pinfunction "1_2") (pintype "input"))
      (node (ref "R7") (pin "2") (pinfunction "1_2") (pintype "input"))
      (node (ref "R9") (pin "2") (pinfunction "1_2") (pintype "input"))
      (node (ref "SR1") (pin "8") (pinfunction "GND_8") (pintype "unspecified"))
      (node (ref "SR2") (pin "8") (pinfunction "GND_8") (pintype "unspecified"))
      (node (ref "SR3") (pin "8") (pinfunction "GND_8") (pintype "unspecified"))
      (node (ref "SR_INPUT") (pin "7") (pinfunction "7_7") (pintype "unspecified"))
      (node (ref "SR_INPUT") (pin "8") (pinfunction "8_8") (pintype "unspecified"))
      (node (ref "SR_OUTPUT") (pin "7") (pinfunction "7_7") (pintype "unspecified"))
      (node (ref "SR_OUTPUT") (pin "8") (pinfunction "8_8") (pintype "unspecified"))
    )
    (net (code "48") (name "Net-(M1-G)") (class "Default")
      (node (ref "M1") (pin "1") (pinfunction "G_1") (pintype "input"))
      (node (ref "M2") (pin "1") (pinfunction "G_1") (pintype "input"))
      (node (ref "R1") (pin "1") (pinfunction "1_1") (pintype "input"))
      (node (ref "R2") (pin "2") (pinfunction "1_2") (pintype "input"))
    )
    (net (code "49") (name "Net-(M1-S)") (class "Default")
      (node (ref "M1") (pin "2") (pinfunction "S_2") (pintype "input"))
      (node (ref "M2") (pin "2") (pinfunction "S_2") (pintype "input"))
    )
    (net (code "50") (name "Net-(M3-G)") (class "Default")
      (node (ref "M3") (pin "1") (pinfunction "G_1") (pintype "input"))
      (node (ref "M4") (pin "1") (pinfunction "G_1") (pintype "input"))
      (node (ref "R3") (pin "1") (pinfunction "1_1") (pintype "input"))
      (node (ref "R4") (pin "2") (pinfunction "1_2") (pintype "input"))
    )
    (net (code "51") (name "Net-(M3-S)") (class "Default")
      (node (ref "M3") (pin "2") (pinfunction "S_2") (pintype "input"))
      (node (ref "M4") (pin "2") (pinfunction "S_2") (pintype "input"))
    )
    (net (code "52") (name "Net-(M5-G)") (class "Default")
      (node (ref "M5") (pin "1") (pinfunction "G_1") (pintype "input"))
      (node (ref "M6") (pin "1") (pinfunction "G_1") (pintype "input"))
      (node (ref "R5") (pin "1") (pinfunction "1_1") (pintype "input"))
      (node (ref "R6") (pin "2") (pinfunction "1_2") (pintype "input"))
    )
    (net (code "53") (name "Net-(M5-S)") (class "Default")
      (node (ref "M5") (pin "2") (pinfunction "S_2") (pintype "input"))
      (node (ref "M6") (pin "2") (pinfunction "S_2") (pintype "input"))
    )
    (net (code "54") (name "Net-(M7-G)") (class "Default")
      (node (ref "M7") (pin "1") (pinfunction "G_1") (pintype "input"))
      (node (ref "M8") (pin "1") (pinfunction "G_1") (pintype "input"))
      (node (ref "R7") (pin "1") (pinfunction "1_1") (pintype "input"))
      (node (ref "R8") (pin "2") (pinfunction "1_2") (pintype "input"))
    )
    (net (code "55") (name "Net-(M7-S)") (class "Default")
      (node (ref "M7") (pin "2") (pinfunction "S_2") (pintype "input"))
      (node (ref "M8") (pin "2") (pinfunction "S_2") (pintype "input"))
    )
    (net (code "56") (name "Net-(M10-G)") (class "Default")
      (node (ref "M10") (pin "1") (pinfunction "G_1") (pintype "input"))
      (node (ref "M9") (pin "1") (pinfunction "G_1") (pintype "input"))
      (node (ref "R10") (pin "2") (pinfunction "1_2") (pintype "input"))
      (node (ref "R9") (pin "1") (pinfunction "1_1") (pintype "input"))
    )
    (net (code "57") (name "Net-(M10-S)") (class "Default")
      (node (ref "M10") (pin "2") (pinfunction "S_2") (pintype "input"))
      (node (ref "M9") (pin "2") (pinfunction "S_2") (pintype "input"))
    )
    (net (code "58") (name "Net-(M11-G)") (class "Default")
      (node (ref "M11") (pin "1") (pinfunction "G_1") (pintype "input"))
      (node (ref "M12") (pin "1") (pinfunction "G_1") (pintype "input"))
      (node (ref "R11") (pin "1") (pinfunction "1_1") (pintype "input"))
      (node (ref "R12") (pin "2") (pinfunction "1_2") (pintype "input"))
    )
    (net (code "59") (name "Net-(M11-S)") (class "Default")
      (node (ref "M11") (pin "2") (pinfunction "S_2") (pintype "input"))
      (node (ref "M12") (pin "2") (pinfunction "S_2") (pintype "input"))
    )
    (net (code "60") (name "Net-(M13-G)") (class "Default")
      (node (ref "M13") (pin "1") (pinfunction "G_1") (pintype "input"))
      (node (ref "M14") (pin "1") (pinfunction "G_1") (pintype "input"))
      (node (ref "R13") (pin "1") (pinfunction "1_1") (pintype "input"))
      (node (ref "R14") (pin "2") (pinfunction "1_2") (pintype "input"))
    )
    (net (code "61") (name "Net-(M13-S)") (class "Default")
      (node (ref "M13") (pin "2") (pinfunction "S_2") (pintype "input"))
      (node (ref "M14") (pin "2") (pinfunction "S_2") (pintype "input"))
    )
    (net (code "62") (name "Net-(M15-G)") (class "Default")
      (node (ref "M15") (pin "1") (pinfunction "G_1") (pintype "input"))
      (node (ref "M16") (pin "1") (pinfunction "G_1") (pintype "input"))
      (node (ref "R15") (pin "1") (pinfunction "1_1") (pintype "input"))
      (node (ref "R16") (pin "2") (pinfunction "1_2") (pintype "input"))
    )
    (net (code "63") (name "Net-(M15-S)") (class "Default")
      (node (ref "M15") (pin "2") (pinfunction "S_2") (pintype "input"))
      (node (ref "M16") (pin "2") (pinfunction "S_2") (pintype "input"))
    )
    (net (code "64") (name "Net-(M17-G)") (class "Default")
      (node (ref "M17") (pin "1") (pinfunction "G_1") (pintype "input"))
      (node (ref "M18") (pin "1") (pinfunction "G_1") (pintype "input"))
      (node (ref "R17") (pin "1") (pinfunction "1_1") (pintype "input"))
      (node (ref "R18") (pin "2") (pinfunction "1_2") (pintype "input"))
    )
    (net (code "65") (name "Net-(M17-S)") (class "Default")
      (node (ref "M17") (pin "2") (pinfunction "S_2") (pintype "input"))
      (node (ref "M18") (pin "2") (pinfunction "S_2") (pintype "input"))
    )
    (net (code "66") (name "Net-(M19-G)") (class "Default")
      (node (ref "M19") (pin "1") (pinfunction "G_1") (pintype "input"))
      (node (ref "M20") (pin "1") (pinfunction "G_1") (pintype "input"))
      (node (ref "R19") (pin "1") (pinfunction "1_1") (pintype "input"))
      (node (ref "R20") (pin "2") (pinfunction "1_2") (pintype "input"))
    )
    (net (code "67") (name "Net-(M19-S)") (class "Default")
      (node (ref "M19") (pin "2") (pinfunction "S_2") (pintype "input"))
      (node (ref "M20") (pin "2") (pinfunction "S_2") (pintype "input"))
    )
    (net (code "68") (name "Net-(M21-G)") (class "Default")
      (node (ref "M21") (pin "1") (pinfunction "G_1") (pintype "input"))
      (node (ref "M22") (pin "1") (pinfunction "G_1") (pintype "input"))
      (node (ref "R21") (pin "1") (pinfunction "1_1") (pintype "input"))
      (node (ref "R22") (pin "2") (pinfunction "1_2") (pintype "input"))
    )
    (net (code "69") (name "Net-(M21-S)") (class "Default")
      (node (ref "M21") (pin "2") (pinfunction "S_2") (pintype "input"))
      (node (ref "M22") (pin "2") (pinfunction "S_2") (pintype "input"))
    )
    (net (code "70") (name "Net-(M23-G)") (class "Default")
      (node (ref "M23") (pin "1") (pinfunction "G_1") (pintype "input"))
      (node (ref "M24") (pin "1") (pinfunction "G_1") (pintype "input"))
      (node (ref "R23") (pin "1") (pinfunction "1_1") (pintype "input"))
      (node (ref "R24") (pin "2") (pinfunction "1_2") (pintype "input"))
    )
    (net (code "71") (name "Net-(M23-S)") (class "Default")
      (node (ref "M23") (pin "2") (pinfunction "S_2") (pintype "input"))
      (node (ref "M24") (pin "2") (pinfunction "S_2") (pintype "input"))
    )
    (net (code "72") (name "Net-(M25-G)") (class "Default")
      (node (ref "M25") (pin "1") (pinfunction "G_1") (pintype "input"))
      (node (ref "M26") (pin "1") (pinfunction "G_1") (pintype "input"))
      (node (ref "R25") (pin "1") (pinfunction "1_1") (pintype "input"))
      (node (ref "R26") (pin "2") (pinfunction "1_2") (pintype "input"))
    )
    (net (code "73") (name "Net-(M25-S)") (class "Default")
      (node (ref "M25") (pin "2") (pinfunction "S_2") (pintype "input"))
      (node (ref "M26") (pin "2") (pinfunction "S_2") (pintype "input"))
    )
    (net (code "74") (name "Net-(M27-G)") (class "Default")
      (node (ref "M27") (pin "1") (pinfunction "G_1") (pintype "input"))
      (node (ref "M28") (pin "1") (pinfunction "G_1") (pintype "input"))
      (node (ref "R27") (pin "2") (pinfunction "1_2") (pintype "input"))
      (node (ref "R28") (pin "1") (pinfunction "1_1") (pintype "input"))
    )
    (net (code "75") (name "Net-(M27-S)") (class "Default")
      (node (ref "M27") (pin "2") (pinfunction "S_2") (pintype "input"))
      (node (ref "M28") (pin "2") (pinfunction "S_2") (pintype "input"))
    )
    (net (code "76") (name "Net-(M29-G)") (class "Default")
      (node (ref "M29") (pin "1") (pinfunction "G_1") (pintype "input"))
      (node (ref "M30") (pin "1") (pinfunction "G_1") (pintype "input"))
      (node (ref "R29") (pin "1") (pinfunction "1_1") (pintype "input"))
      (node (ref "R30") (pin "2") (pinfunction "1_2") (pintype "input"))
    )
    (net (code "77") (name "Net-(M29-S)") (class "Default")
      (node (ref "M29") (pin "2") (pinfunction "S_2") (pintype "input"))
      (node (ref "M30") (pin "2") (pinfunction "S_2") (pintype "input"))
    )
    (net (code "78") (name "Net-(M31-G)") (class "Default")
      (node (ref "M31") (pin "1") (pinfunction "G_1") (pintype "input"))
      (node (ref "M32") (pin "1") (pinfunction "G_1") (pintype "input"))
      (node (ref "R31") (pin "2") (pinfunction "1_2") (pintype "input"))
      (node (ref "R32") (pin "1") (pinfunction "1_1") (pintype "input"))
    )
    (net (code "79") (name "Net-(M31-S)") (class "Default")
      (node (ref "M31") (pin "2") (pinfunction "S_2") (pintype "input"))
      (node (ref "M32") (pin "2") (pinfunction "S_2") (pintype "input"))
    )
    (net (code "80") (name "Net-(M33-G)") (class "Default")
      (node (ref "M33") (pin "1") (pinfunction "G_1") (pintype "input"))
      (node (ref "M34") (pin "1") (pinfunction "G_1") (pintype "input"))
      (node (ref "R33") (pin "1") (pinfunction "1_1") (pintype "input"))
      (node (ref "R34") (pin "2") (pinfunction "1_2") (pintype "input"))
    )
    (net (code "81") (name "Net-(M33-S)") (class "Default")
      (node (ref "M33") (pin "2") (pinfunction "S_2") (pintype "input"))
      (node (ref "M34") (pin "2") (pinfunction "S_2") (pintype "input"))
    )
    (net (code "82") (name "Net-(M35-G)") (class "Default")
      (node (ref "M35") (pin "1") (pinfunction "G_1") (pintype "input"))
      (node (ref "M36") (pin "1") (pinfunction "G_1") (pintype "input"))
      (node (ref "R35") (pin "1") (pinfunction "1_1") (pintype "input"))
      (node (ref "R36") (pin "2") (pinfunction "1_2") (pintype "input"))
    )
    (net (code "83") (name "Net-(M35-S)") (class "Default")
      (node (ref "M35") (pin "2") (pinfunction "S_2") (pintype "input"))
      (node (ref "M36") (pin "2") (pinfunction "S_2") (pintype "input"))
    )
    (net (code "84") (name "Net-(M37-G)") (class "Default")
      (node (ref "M37") (pin "1") (pinfunction "G_1") (pintype "input"))
      (node (ref "M38") (pin "1") (pinfunction "G_1") (pintype "input"))
      (node (ref "R37") (pin "1") (pinfunction "1_1") (pintype "input"))
      (node (ref "R38") (pin "2") (pinfunction "1_2") (pintype "input"))
    )
    (net (code "85") (name "Net-(M37-S)") (class "Default")
      (node (ref "M37") (pin "2") (pinfunction "S_2") (pintype "input"))
      (node (ref "M38") (pin "2") (pinfunction "S_2") (pintype "input"))
    )
    (net (code "86") (name "Net-(M39-G)") (class "Default")
      (node (ref "M39") (pin "1") (pinfunction "G_1") (pintype "input"))
      (node (ref "M40") (pin "1") (pinfunction "G_1") (pintype "input"))
      (node (ref "R39") (pin "1") (pinfunction "1_1") (pintype "input"))
      (node (ref "R40") (pin "2") (pinfunction "1_2") (pintype "input"))
    )
    (net (code "87") (name "Net-(M39-S)") (class "Default")
      (node (ref "M39") (pin "2") (pinfunction "S_2") (pintype "input"))
      (node (ref "M40") (pin "2") (pinfunction "S_2") (pintype "input"))
    )
    (net (code "88") (name "Net-(M41-G)") (class "Default")
      (node (ref "M41") (pin "1") (pinfunction "G_1") (pintype "input"))
      (node (ref "M42") (pin "1") (pinfunction "G_1") (pintype "input"))
      (node (ref "R41") (pin "1") (pinfunction "1_1") (pintype "input"))
      (node (ref "R42") (pin "2") (pinfunction "1_2") (pintype "input"))
    )
    (net (code "89") (name "Net-(M41-S)") (class "Default")
      (node (ref "M41") (pin "2") (pinfunction "S_2") (pintype "input"))
      (node (ref "M42") (pin "2") (pinfunction "S_2") (pintype "input"))
    )
    (net (code "90") (name "Net-(M43-G)") (class "Default")
      (node (ref "M43") (pin "1") (pinfunction "G_1") (pintype "input"))
      (node (ref "M44") (pin "1") (pinfunction "G_1") (pintype "input"))
      (node (ref "R47") (pin "1") (pinfunction "1_1") (pintype "input"))
      (node (ref "R48") (pin "2") (pinfunction "1_2") (pintype "input"))
    )
    (net (code "91") (name "Net-(M43-S)") (class "Default")
      (node (ref "M43") (pin "2") (pinfunction "S_2") (pintype "input"))
      (node (ref "M44") (pin "2") (pinfunction "S_2") (pintype "input"))
    )
    (net (code "92") (name "Net-(M45-G)") (class "Default")
      (node (ref "M45") (pin "1") (pinfunction "G_1") (pintype "input"))
      (node (ref "M46") (pin "1") (pinfunction "G_1") (pintype "input"))
      (node (ref "R49") (pin "1") (pinfunction "1_1") (pintype "input"))
      (node (ref "R50") (pin "2") (pinfunction "1_2") (pintype "input"))
    )
    (net (code "93") (name "Net-(M45-S)") (class "Default")
      (node (ref "M45") (pin "2") (pinfunction "S_2") (pintype "input"))
      (node (ref "M46") (pin "2") (pinfunction "S_2") (pintype "input"))
    )
    (net (code "94") (name "Net-(SR1-Q&apos;H)") (class "Default")
      (node (ref "SR1") (pin "9") (pinfunction "Q&apos;H_9") (pintype "unspecified"))
      (node (ref "SR2") (pin "14") (pinfunction "SER_14") (pintype "unspecified"))
    )
    (net (code "95") (name "Net-(SR1-SER)") (class "Default")
      (node (ref "SR1") (pin "14") (pinfunction "SER_14") (pintype "unspecified"))
      (node (ref "SR_INPUT") (pin "2") (pinfunction "2_2") (pintype "unspecified"))
    )
    (net (code "96") (name "Net-(SR2-Q&apos;H)") (class "Default")
      (node (ref "SR2") (pin "9") (pinfunction "Q&apos;H_9") (pintype "unspecified"))
      (node (ref "SR3") (pin "14") (pinfunction "SER_14") (pintype "unspecified"))
    )
    (net (code "97") (name "Net-(SR3-Q&apos;H)") (class "Default")
      (node (ref "SR3") (pin "9") (pinfunction "Q&apos;H_9") (pintype "unspecified"))
      (node (ref "SR_OUTPUT") (pin "2") (pinfunction "2_2") (pintype "unspecified"))
    )
    (net (code "98") (name "unconnected-(SR3-QH-Pad7)") (class "Default")
      (node (ref "SR3") (pin "7") (pinfunction "QH_7") (pintype "unspecified+no_connect"))
    )
  )
)
